# LP_ECG_ECG-X01.net
KiCad netlist of a schematic drawn in Altium Designer
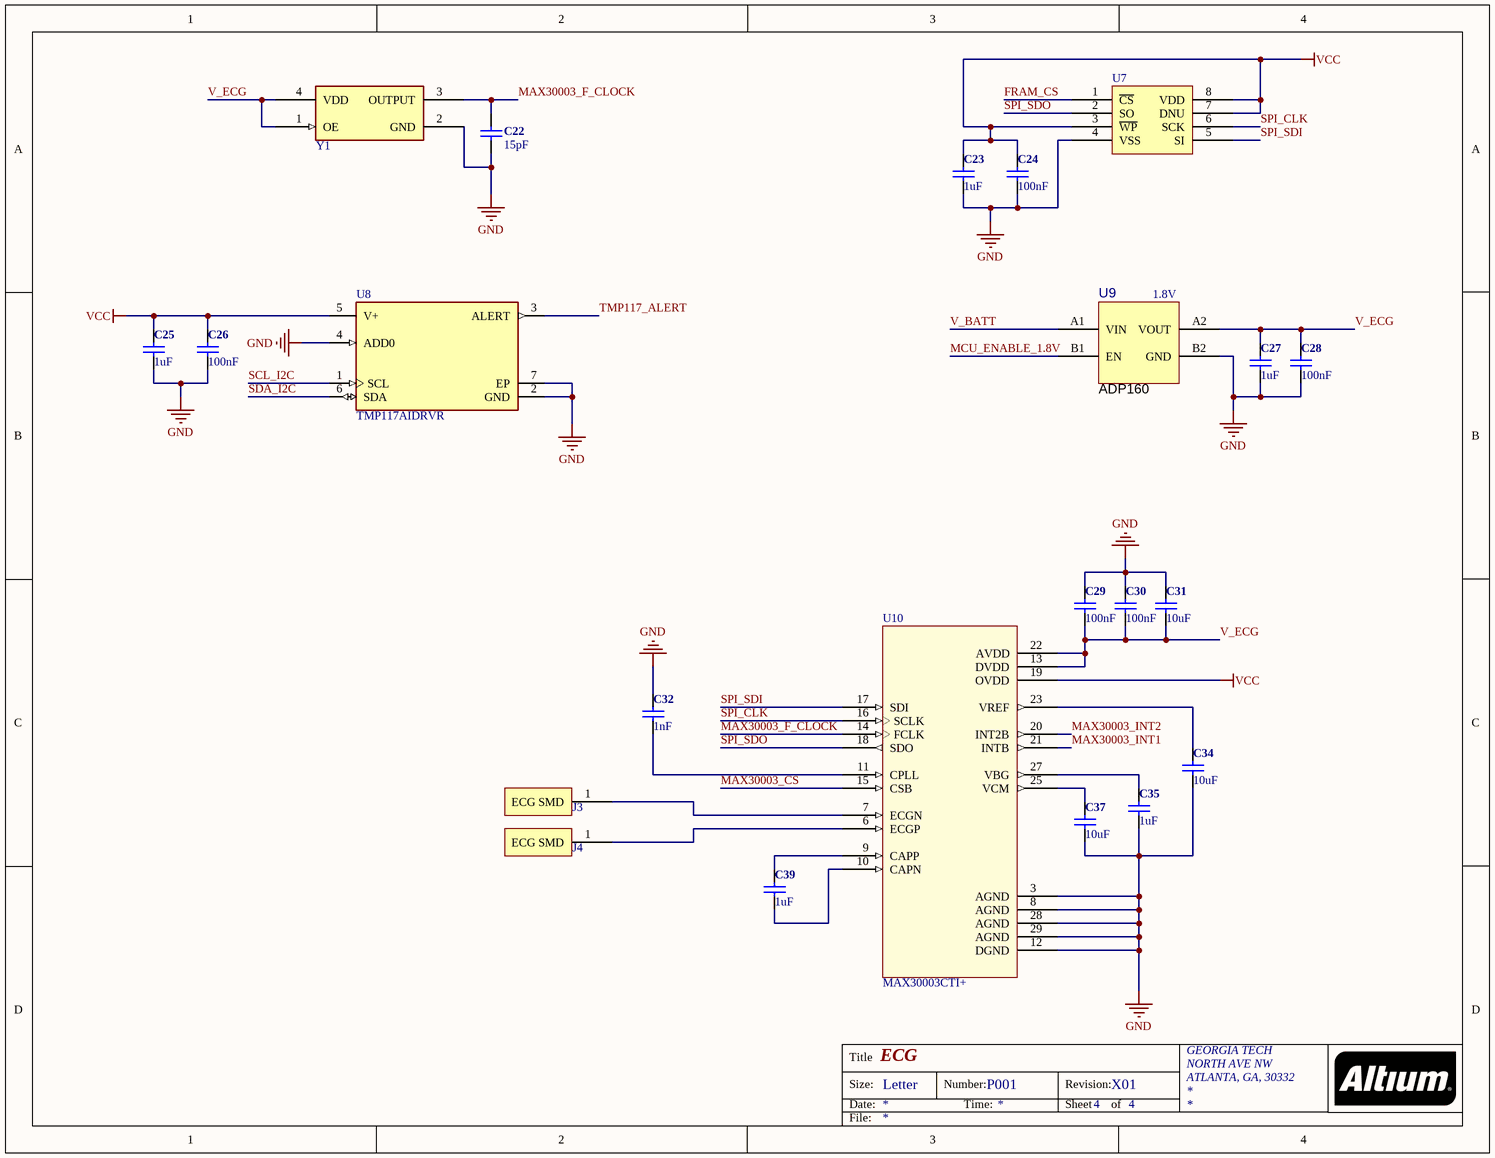
[diagram p0: LP_ECG_ECG-X01.SchDoc]

(export (version "E")
  (design (tool "Eeschema 10.0.6"))
  (components
    (comp (ref "C22")
      (value "15pF")
      (footprint "C0402")
      (fields
        (field (name "MANUFACTURER") "Murata")
        (field (name "MANUFACTURER PART NUMBER") "GJM1555C1H150FB01D")
        (field (name "TOLERANCE") "1%")
      )
      (libsource (lib "LP_ECG-X01") (part "C-0402(1005)"))
    )
    (comp (ref "C23")
      (value "1uF")
      (footprint "C0402")
      (fields
        (field (name "MANUFACTURER") "Yageo")
        (field (name "MANUFACTURER PART NUMBER") "CC0402MRX5R5BB105")
        (field (name "TOLERANCE") "20%")
      )
      (libsource (lib "LP_ECG-X01") (part "C-0402(1005)"))
    )
    (comp (ref "C24")
      (value "100nF")
      (footprint "C0402")
      (fields
        (field (name "MANUFACTURER") "Taiyo Yuden")
        (field (name "MANUFACTURER PART NUMBER") "TMK105BJ104KV-F")
        (field (name "TOLERANCE") "10%")
      )
      (libsource (lib "LP_ECG-X01") (part "C-0402(1005)"))
    )
    (comp (ref "C25")
      (value "1uF")
      (footprint "C0402")
      (fields
        (field (name "MANUFACTURER") "Yageo")
        (field (name "MANUFACTURER PART NUMBER") "CC0402MRX5R5BB105")
        (field (name "TOLERANCE") "20%")
      )
      (libsource (lib "LP_ECG-X01") (part "C-0402(1005)"))
    )
    (comp (ref "C26")
      (value "100nF")
      (footprint "C0402")
      (fields
        (field (name "MANUFACTURER") "Taiyo Yuden")
        (field (name "MANUFACTURER PART NUMBER") "TMK105BJ104KV-F")
        (field (name "TOLERANCE") "10%")
      )
      (libsource (lib "LP_ECG-X01") (part "C-0402(1005)"))
    )
    (comp (ref "C27")
      (value "1uF")
      (footprint "C0402")
      (fields
        (field (name "MANUFACTURER") "Yageo")
        (field (name "MANUFACTURER PART NUMBER") "CC0402MRX5R5BB105")
        (field (name "TOLERANCE") "20%")
      )
      (libsource (lib "LP_ECG-X01") (part "C-0402(1005)"))
    )
    (comp (ref "C28")
      (value "100nF")
      (footprint "C0402")
      (fields
        (field (name "MANUFACTURER") "Taiyo Yuden")
        (field (name "MANUFACTURER PART NUMBER") "TMK105BJ104KV-F")
        (field (name "TOLERANCE") "10%")
      )
      (libsource (lib "LP_ECG-X01") (part "C-0402(1005)"))
    )
    (comp (ref "C29")
      (value "100nF")
      (footprint "C0402")
      (fields
        (field (name "MANUFACTURER") "Taiyo Yuden")
        (field (name "MANUFACTURER PART NUMBER") "TMK105BJ104KV-F")
      )
      (libsource (lib "LP_ECG-X01") (part "C-0402(1005)"))
    )
    (comp (ref "C30")
      (value "100nF")
      (footprint "C0402")
      (fields
        (field (name "MANUFACTURER") "Taiyo Yuden")
        (field (name "MANUFACTURER PART NUMBER") "TMK105BJ104KV-F")
      )
      (libsource (lib "LP_ECG-X01") (part "C-0402(1005)"))
    )
    (comp (ref "C31")
      (value "10uF")
      (footprint "C0402")
      (fields
        (field (name "MANUFACTURER") "Kyocera AVX")
        (field (name "MANUFACTURER PART NUMBER") "0402ZD106MAT2A")
      )
      (libsource (lib "LP_ECG-X01") (part "C-0402(1005)"))
    )
    (comp (ref "C32")
      (value "1nF")
      (footprint "C0402")
      (description "Ceramic Capacitor, Multilayer, Ceramic, 10V, 5% +Tol, 5% -Tol, C0G, -/+30ppm/Cel TC, 0.001uF, 0402")
      (fields
        (field (name "MANUFACTURER") "KEMET")
        (field (name "MANUFACTURER PART NUMBER") "C0402C102J8GAC7867")
      )
      (libsource (lib "LP_ECG-X01") (part "C-0402(1005)"))
    )
    (comp (ref "C34")
      (value "10uF")
      (footprint "C0402")
      (fields
        (field (name "MANUFACTURER") "Kyocera AVX")
        (field (name "MANUFACTURER PART NUMBER") "0402ZD106MAT2A")
      )
      (libsource (lib "LP_ECG-X01") (part "C-0402(1005)"))
    )
    (comp (ref "C35")
      (value "1uF")
      (footprint "C0402")
      (fields
        (field (name "MANUFACTURER") "Yageo")
        (field (name "MANUFACTURER PART NUMBER") "CC0402MRX5R5BB105")
        (field (name "TOLERANCE") "20%")
      )
      (libsource (lib "LP_ECG-X01") (part "C-0402(1005)"))
    )
    (comp (ref "C37")
      (value "10uF")
      (footprint "C0402")
      (fields
        (field (name "MANUFACTURER") "Kyocera AVX")
        (field (name "MANUFACTURER PART NUMBER") "0402ZD106MAT2A")
      )
      (libsource (lib "LP_ECG-X01") (part "C-0402(1005)"))
    )
    (comp (ref "C39")
      (value "1uF")
      (footprint "C0402")
      (fields
        (field (name "MANUFACTURER") "Yageo")
        (field (name "MANUFACTURER PART NUMBER") "CC0402MRX5R5BB105")
        (field (name "TOLERANCE") "20%")
      )
      (libsource (lib "LP_ECG-X01") (part "C-0402(1005)"))
    )
    (comp (ref "J3")
      (value "ECG_SMD_CONNECTOR")
      (footprint "ecg_connector")
      (description "SMD CONNECTOR FOR ECG")
      (libsource (lib "LP_ECG-X01") (part "ECG_SMD_CONNECTOR"))
    )
    (comp (ref "J4")
      (value "ECG_SMD_CONNECTOR")
      (footprint "ecg_connector")
      (description "SMD CONNECTOR FOR ECG")
      (libsource (lib "LP_ECG-X01") (part "ECG_SMD_CONNECTOR"))
    )
    (comp (ref "U7")
      (value "8 MB FRAM")
      (footprint "GQFN-8")
      (description "Memory Circuit, 8 MB FRAM")
      (fields
        (field (name "MANUFACTURER") "Cypress")
        (field (name "MANUFACTURER PART NUMBER") "CY15B108QI-20LPXI")
      )
      (libsource (lib "LP_ECG-X01") (part "CY15B108QI"))
    )
    (comp (ref "U8")
      (value "TMP117AIDRVR")
      (footprint "TMP117AIDRVR")
      (description "TEMPERATURE SENSOR")
      (fields
        (field (name "OCTOPART") "https://octopart.com/tmp117aidrvr-texas+instruments-95511044")
        (field (name "MANUFACTURER") "Texas Instruments")
      )
      (libsource (lib "LP_ECG-X01") (part "bceab6869a9cb85cf5675529ee35ce4"))
    )
    (comp (ref "U9")
      (value "ADP160")
      (footprint "ADP160")
      (description "Fixed Positive LDO Regulator, 1.8V, 0.195V Dropout, CMOS, PBGA4")
      (fields
        (field (name "MANUFACTURER") "Analog Devices")
        (field (name "MANUFACTURER PART NUMBER") "ADP160ACBZ-1.8-R7")
        (field (name "OUTPUT VOLTAGE") "1.8V")
      )
      (libsource (lib "LP_ECG-X01") (part "ADP160-1_8V"))
    )
    (comp (ref "U10")
      (value "MAX30003CTI+")
      (footprint "QFN50P500X500X80-29N")
      (description "Analog Circuit, 1 Func, CMOS")
      (fields (field (name "MANUFACTURER") "Maxim"))
      (libsource (lib "LP_ECG-X01") (part "MAX30003CTI+"))
    )
    (comp (ref "Y1")
      (value "OSCILLATOR-32.768KHZ")
      (footprint "OSCILLATOR_4-SMD")
      (description "Oscillator Xo 0.032768MHZ ±25PPM 15PF Lvcmos/lvttl 55% 1.8V 4-PIN Csmd T/r")
      (fields
        (field (name "MANUFACTURER") "Diodes Inc.")
        (field (name "MANUFACTURER PART NUMBER") "KX2013B0032.768000")
      )
      (libsource (lib "LP_ECG-X01") (part "OSCILLATOR_32K768"))
    )
  )
  (nets
    (net (code "1") (name "/FRAM_CS") (class "Default")
      (node (ref "U7") (pin "1") (pinfunction "~{CS}_1") (pintype "passive"))
    )
    (net (code "2") (name "/MAX30003_CS") (class "Default")
      (node (ref "U10") (pin "15") (pinfunction "CSB_15") (pintype "input"))
    )
    (net (code "3") (name "/MAX30003_F_CLOCK") (class "Default")
      (node (ref "C22") (pin "1") (pinfunction "1_1") (pintype "passive"))
      (node (ref "U10") (pin "14") (pinfunction "FCLK_14") (pintype "input"))
      (node (ref "Y1") (pin "3") (pinfunction "OUTPUT_3") (pintype "passive"))
    )
    (net (code "4") (name "/MAX30003_INT1") (class "Default")
      (node (ref "U10") (pin "21") (pinfunction "INTB_21") (pintype "output"))
    )
    (net (code "5") (name "/MAX30003_INT2") (class "Default")
      (node (ref "U10") (pin "20") (pinfunction "INT2B_20") (pintype "output"))
    )
    (net (code "6") (name "/MCU_ENABLE_1.8V") (class "Default")
      (node (ref "U9") (pin "B1") (pinfunction "EN_B1") (pintype "passive"))
    )
    (net (code "7") (name "/SCL_I2C") (class "Default")
      (node (ref "U8") (pin "1") (pinfunction "SCL_1") (pintype "input"))
    )
    (net (code "8") (name "/SDA_I2C") (class "Default")
      (node (ref "U8") (pin "6") (pinfunction "SDA_6") (pintype "bidirectional"))
    )
    (net (code "9") (name "/SPI_CLK") (class "Default")
      (node (ref "U10") (pin "16") (pinfunction "SCLK_16") (pintype "input"))
      (node (ref "U7") (pin "6") (pinfunction "SCK_6") (pintype "passive"))
    )
    (net (code "10") (name "/SPI_SDI") (class "Default")
      (node (ref "U10") (pin "17") (pinfunction "SDI_17") (pintype "input"))
      (node (ref "U7") (pin "5") (pinfunction "SI_5") (pintype "passive"))
    )
    (net (code "11") (name "/SPI_SDO") (class "Default")
      (node (ref "U10") (pin "18") (pinfunction "SDO_18") (pintype "output"))
      (node (ref "U7") (pin "2") (pinfunction "SO_2") (pintype "passive"))
    )
    (net (code "12") (name "/TMP117_ALERT") (class "Default")
      (node (ref "U8") (pin "3") (pinfunction "ALERT_3") (pintype "output"))
    )
    (net (code "13") (name "/V_BATT") (class "Default")
      (node (ref "U9") (pin "A1") (pinfunction "VIN_A1") (pintype "passive"))
    )
    (net (code "14") (name "/V_ECG") (class "Default")
      (node (ref "C27") (pin "1") (pinfunction "1_1") (pintype "passive"))
      (node (ref "C28") (pin "2") (pinfunction "2_2") (pintype "passive"))
      (node (ref "C29") (pin "2") (pinfunction "2_2") (pintype "passive"))
      (node (ref "C30") (pin "2") (pinfunction "2_2") (pintype "passive"))
      (node (ref "C31") (pin "2") (pinfunction "2_2") (pintype "passive"))
      (node (ref "U10") (pin "13") (pinfunction "DVDD_13") (pintype "power_in"))
      (node (ref "U10") (pin "22") (pinfunction "AVDD_22") (pintype "power_in"))
      (node (ref "U9") (pin "A2") (pinfunction "VOUT_A2") (pintype "passive"))
      (node (ref "Y1") (pin "1") (pinfunction "OE_1") (pintype "input"))
      (node (ref "Y1") (pin "4") (pinfunction "VDD_4") (pintype "power_in"))
    )
    (net (code "15") (name "GND") (class "Default")
      (node (ref "C22") (pin "2") (pinfunction "2_2") (pintype "passive"))
      (node (ref "C23") (pin "2") (pinfunction "2_2") (pintype "passive"))
      (node (ref "C24") (pin "1") (pinfunction "1_1") (pintype "passive"))
      (node (ref "C25") (pin "2") (pinfunction "2_2") (pintype "passive"))
      (node (ref "C26") (pin "1") (pinfunction "1_1") (pintype "passive"))
      (node (ref "C27") (pin "2") (pinfunction "2_2") (pintype "passive"))
      (node (ref "C28") (pin "1") (pinfunction "1_1") (pintype "passive"))
      (node (ref "C29") (pin "1") (pinfunction "1_1") (pintype "passive"))
      (node (ref "C30") (pin "1") (pinfunction "1_1") (pintype "passive"))
      (node (ref "C31") (pin "1") (pinfunction "1_1") (pintype "passive"))
      (node (ref "C32") (pin "1") (pinfunction "1_1") (pintype "passive"))
      (node (ref "C34") (pin "2") (pinfunction "2_2") (pintype "passive"))
      (node (ref "C35") (pin "2") (pinfunction "2_2") (pintype "passive"))
      (node (ref "C37") (pin "2") (pinfunction "2_2") (pintype "passive"))
      (node (ref "U10") (pin "12") (pinfunction "DGND_12") (pintype "power_in"))
      (node (ref "U10") (pin "28") (pinfunction "AGND_28") (pintype "power_in"))
      (node (ref "U10") (pin "29") (pinfunction "AGND_29") (pintype "power_in"))
      (node (ref "U10") (pin "3") (pinfunction "AGND_3") (pintype "power_in"))
      (node (ref "U10") (pin "8") (pinfunction "AGND_8") (pintype "power_in"))
      (node (ref "U7") (pin "4") (pinfunction "VSS_4") (pintype "passive"))
      (node (ref "U8") (pin "2") (pinfunction "GND_2") (pintype "power_in"))
      (node (ref "U8") (pin "4") (pinfunction "ADD0_4") (pintype "input"))
      (node (ref "U8") (pin "7") (pinfunction "EP_7") (pintype "passive"))
      (node (ref "U9") (pin "B2") (pinfunction "GND_B2") (pintype "passive"))
      (node (ref "Y1") (pin "2") (pinfunction "GND_2") (pintype "power_in"))
    )
    (net (code "16") (name "Net-(J3-ECG_SMD)") (class "Default")
      (node (ref "J3") (pin "1") (pinfunction "ECG_SMD_1") (pintype "passive"))
      (node (ref "U10") (pin "7") (pinfunction "ECGN_7") (pintype "input"))
    )
    (net (code "17") (name "Net-(J4-ECG_SMD)") (class "Default")
      (node (ref "J4") (pin "1") (pinfunction "ECG_SMD_1") (pintype "passive"))
      (node (ref "U10") (pin "6") (pinfunction "ECGP_6") (pintype "input"))
    )
    (net (code "18") (name "Net-(U10-CAPN)") (class "Default")
      (node (ref "C39") (pin "2") (pinfunction "2_2") (pintype "passive"))
      (node (ref "U10") (pin "10") (pinfunction "CAPN_10") (pintype "input"))
    )
    (net (code "19") (name "Net-(U10-CAPP)") (class "Default")
      (node (ref "C39") (pin "1") (pinfunction "1_1") (pintype "passive"))
      (node (ref "U10") (pin "9") (pinfunction "CAPP_9") (pintype "input"))
    )
    (net (code "20") (name "Net-(U10-CPLL)") (class "Default")
      (node (ref "C32") (pin "2") (pinfunction "2_2") (pintype "passive"))
      (node (ref "U10") (pin "11") (pinfunction "CPLL_11") (pintype "input"))
    )
    (net (code "21") (name "Net-(U10-VBG)") (class "Default")
      (node (ref "C35") (pin "1") (pinfunction "1_1") (pintype "passive"))
      (node (ref "U10") (pin "27") (pinfunction "VBG_27") (pintype "output"))
    )
    (net (code "22") (name "Net-(U10-VCM)") (class "Default")
      (node (ref "C37") (pin "1") (pinfunction "1_1") (pintype "passive"))
      (node (ref "U10") (pin "25") (pinfunction "VCM_25") (pintype "output"))
    )
    (net (code "23") (name "Net-(U10-VREF)") (class "Default")
      (node (ref "C34") (pin "1") (pinfunction "1_1") (pintype "passive"))
      (node (ref "U10") (pin "23") (pinfunction "VREF_23") (pintype "output"))
    )
    (net (code "24") (name "VCC") (class "Default")
      (node (ref "C23") (pin "1") (pinfunction "1_1") (pintype "passive"))
      (node (ref "C24") (pin "2") (pinfunction "2_2") (pintype "passive"))
      (node (ref "C25") (pin "1") (pinfunction "1_1") (pintype "passive"))
      (node (ref "C26") (pin "2") (pinfunction "2_2") (pintype "passive"))
      (node (ref "U10") (pin "19") (pinfunction "OVDD_19") (pintype "power_in"))
      (node (ref "U7") (pin "3") (pinfunction "~{WP}_3") (pintype "passive"))
      (node (ref "U7") (pin "7") (pinfunction "DNU_7") (pintype "passive"))
      (node (ref "U7") (pin "8") (pinfunction "VDD_8") (pintype "passive"))
      (node (ref "U8") (pin "5") (pinfunction "V+_5") (pintype "power_in"))
    )
  )
)
